# IR_LED.net
KiCad netlist of a schematic drawn in EAGLE
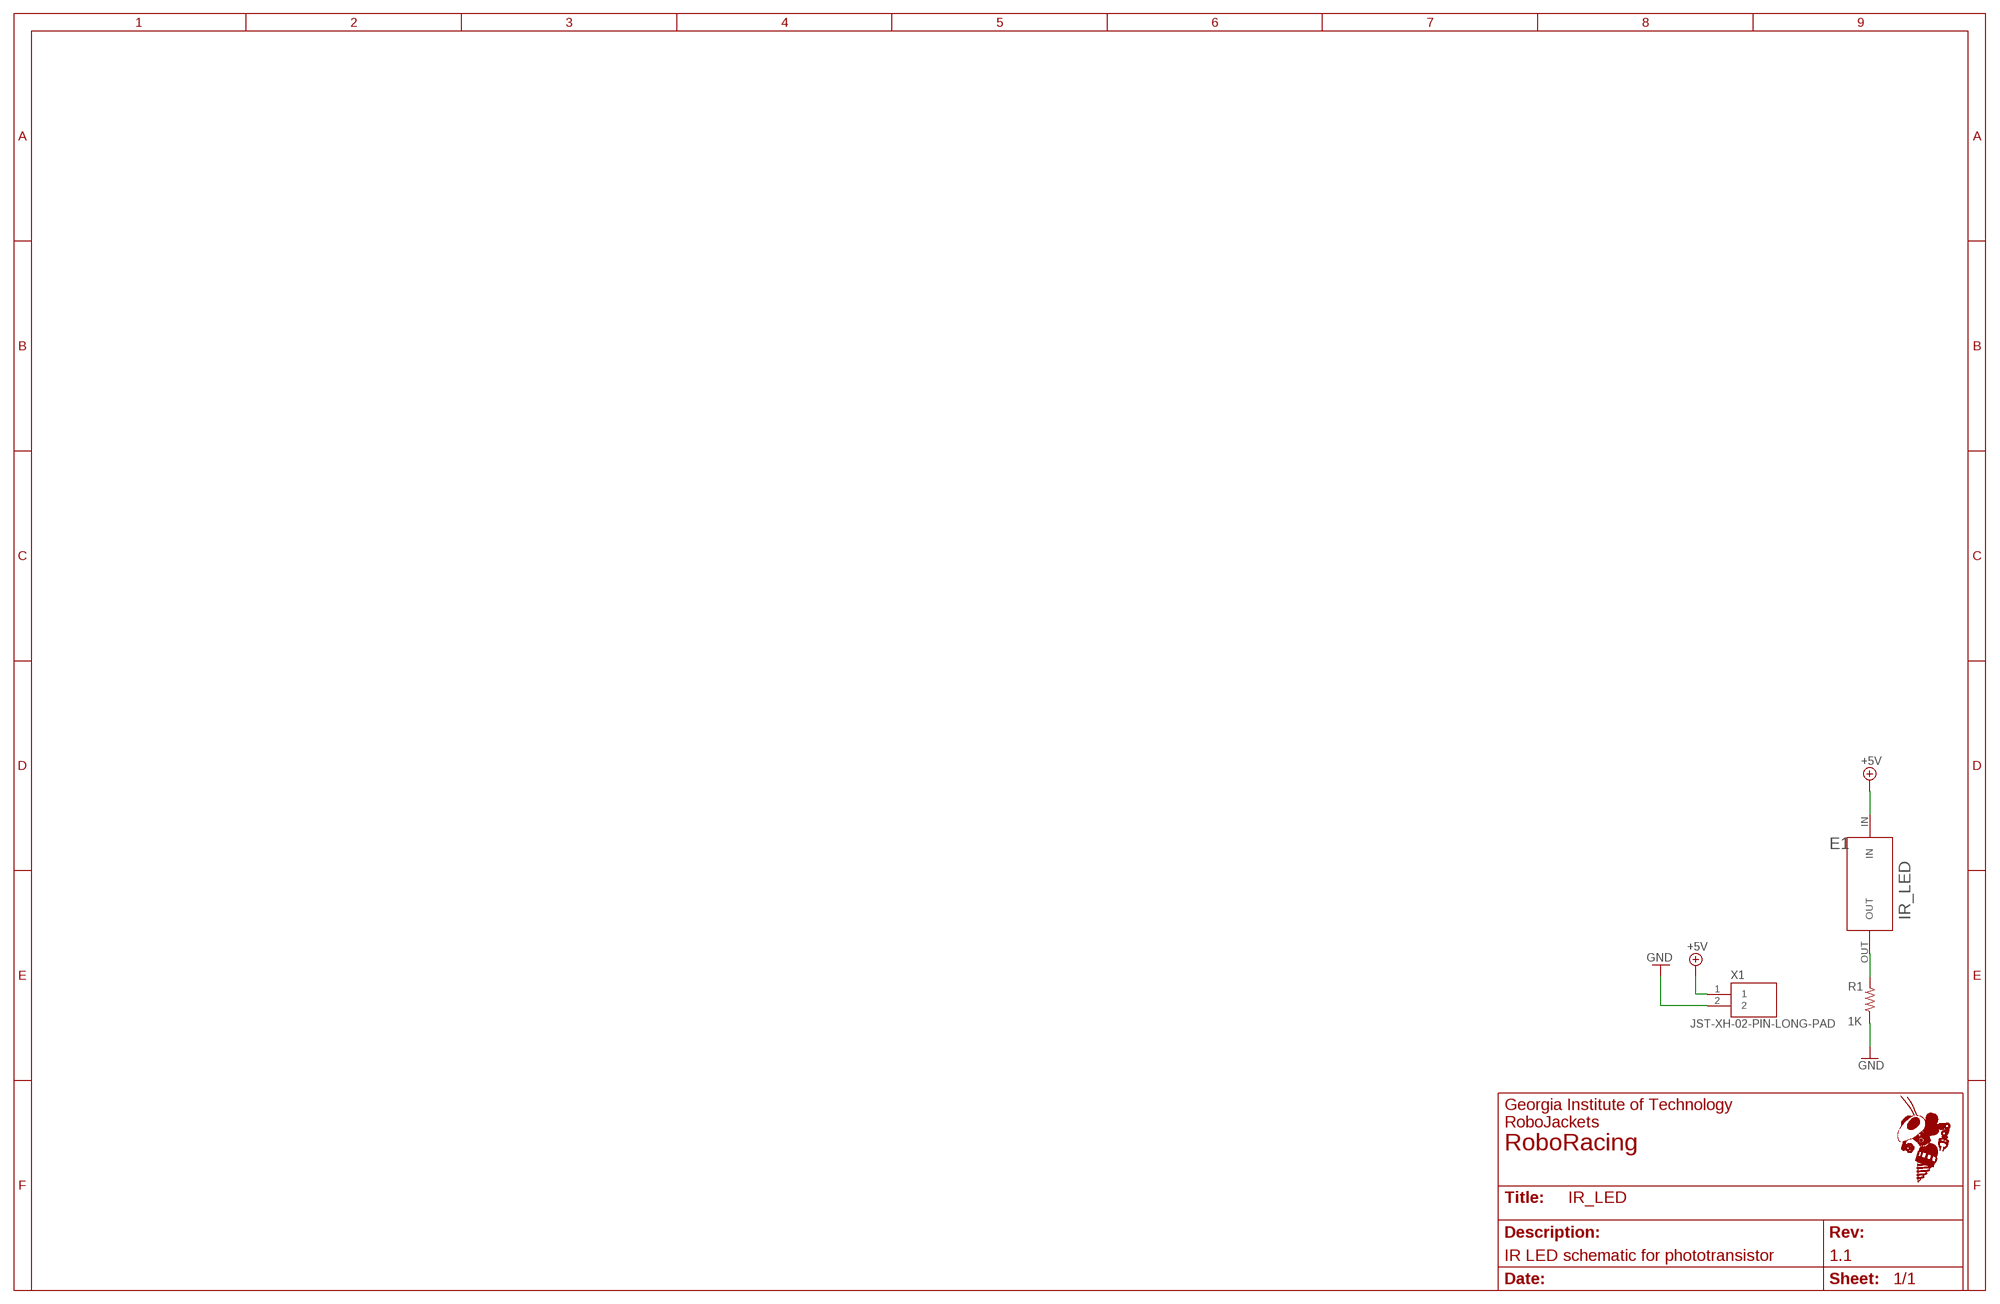
[diagram p0: schematic, sheet 1]

(export (version "E")
  (design (tool "Eeschema 10.0.6"))
  (components
    (comp (ref "E1")
      (value "IR_LED")
      (footprint "eagle-import:STD_FP")
      (libsource (lib "eagle-import") (part "IR_LED"))
    )
    (comp (ref "R1")
      (value "1K")
      (footprint "eagle-import:R0603")
      (libsource (lib "eagle-import") (part "R-US_R0603"))
    )
    (comp (ref "X1")
      (value "JST-XH-02-PIN-LONG-PAD")
      (footprint "eagle-import:JST-XH-02-PACKAGE-LONG-PAD")
      (libsource (lib "eagle-import") (part "JST-XH-02-PIN-LONG-PAD"))
    )
  )
  (nets
    (net (code "1") (name "+5V") (class "Default")
      (node (ref "E1") (pin "IN") (pinfunction "IN_IN") (pintype "input"))
      (node (ref "X1") (pin "1") (pinfunction "1_1") (pintype "passive"))
    )
    (net (code "2") (name "GND") (class "Default")
      (node (ref "R1") (pin "1") (pinfunction "1_1") (pintype "passive"))
      (node (ref "X1") (pin "2") (pinfunction "2_2") (pintype "passive"))
    )
    (net (code "3") (name "Net-(E1-PadOUT)") (class "Default")
      (node (ref "E1") (pin "OUT") (pinfunction "OUT_OUT") (pintype "output"))
      (node (ref "R1") (pin "2") (pinfunction "2_2") (pintype "passive"))
    )
  )
)
